# Sheet2.net
KiCad netlist of a schematic drawn in Altium Designer
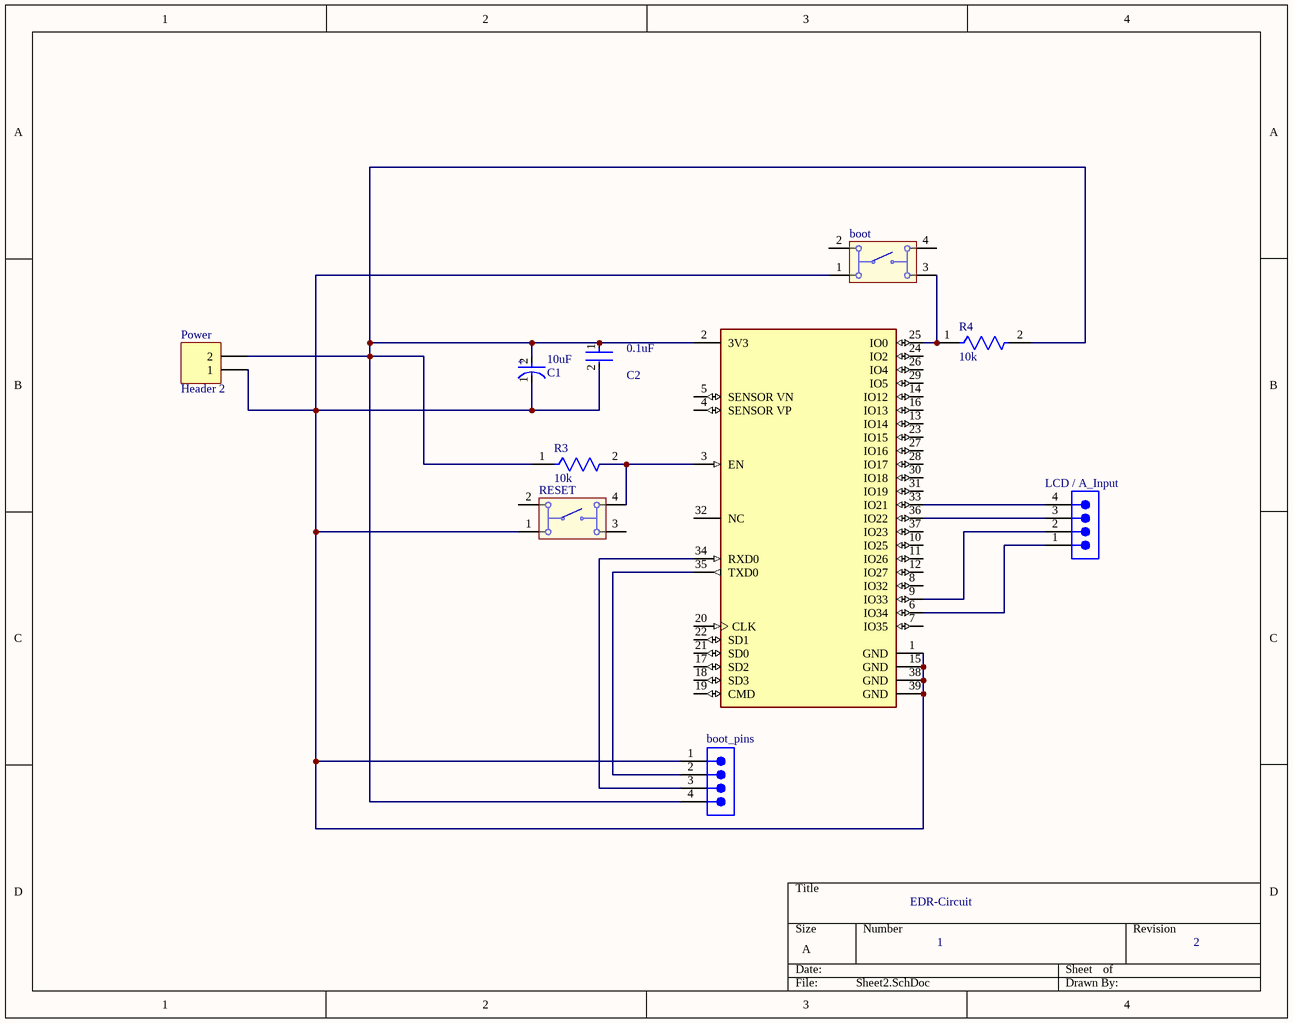
[diagram p0: Sheet2.SchDoc]

(export (version "E")
  (design (tool "Eeschema 10.0.6"))
  (components
    (comp (ref "0.1uF")
      (value "C2")
      (footprint "FP-RCE0DB-MFG")
      (description "Cap Ceramic 100nF 50V X7R ±10% Radial 2.5mm +125°C Ammo Pack")
      (fields (field (name "TOLERANCE") "10%"))
      (libsource (lib "Altium Content Vault") (part "b4654b650e69147ec39a6b967a45e02"))
    )
    (comp (ref "10uF")
      (value "C1")
      (footprint "FP-RAD-TH-D_10_0_5-L_16_1-MFG")
      (description "Aluminum Electrolytic Capacitors (Radial Lead Type) AEC-Q200 Qualified 1000uF ±20% 10V")
      (fields (field (name "VOLTAGE") "10V") (field (name "TOLERANCE") "20%"))
      (libsource (lib "Altium Content Vault") (part "a00bbbee19879c290e62620ae7e47b1"))
    )
    (comp (ref "boot")
      (value "430471025826")
      (footprint "430471025826")
      (description "WS-TASV SMD Tact Switch 6X6 mm")
      (fields (field (name "MANUFACTURER") "Wuerth Elektronik"))
      (libsource (lib "Altium Content Vault") (part "WE-TACT-SW-4_A"))
    )
    (comp (ref "boot_pins")
      (value "TSW-104-08-L-S")
      (footprint "SMTC-TSW-104-08-X-S")
      (description "0.025\" SQ Post Header, Through-hole, Vertical, -55 to 125 degC, 2.54 mm Pitch, 4-Pin, Male, RoHS")
      (fields (field (name "MANUFACTURER") "Samtec"))
      (libsource (lib "Altium Content Vault") (part "SMTC-TSW-104-08-X-S"))
    )
    (comp (ref "esp32")
      (value "ESP32-WROOM-32D")
      (footprint "FP-ESP32-WROOM-32D-MFG")
      (description "WIFI MODULE 32MBITS SPI FLASH")
      (fields
        (field (name "OCTOPART") "https://octopart.com/esp32-wroom-32d-espressif+systems-91040050")
        (field (name "MANUFACTURER") "Espressif Systems")
      )
      (libsource (lib "Altium Content Vault") (part "a031a76f8c27026a7a7f4657ff233a3"))
    )
    (comp (ref "LCD / A_Input")
      (value "TSW-104-08-L-S")
      (footprint "SMTC-TSW-104-08-X-S")
      (description "0.025\" SQ Post Header, Through-hole, Vertical, -55 to 125 degC, 2.54 mm Pitch, 4-Pin, Male, RoHS")
      (fields (field (name "MANUFACTURER") "Samtec"))
      (libsource (lib "Altium Content Vault") (part "SMTC-TSW-104-08-X-S"))
    )
    (comp (ref "Power")
      (value "Header 2")
      (footprint "HDR1X2")
      (description "Header, 2-Pin")
      (fields (field (name "PUBLISHER") "Altium Limited"))
      (libsource (lib "University of Moratuwa") (part "Header 2H"))
    )
    (comp (ref "R3")
      (value "10k")
      (footprint "FP-MBB0207-MFG")
      (description "RES 10K OHM 0.6W 1% AXIAL")
      (fields (field (name "TOLERANCE") "1%"))
      (libsource (lib "Altium Content Vault") (part "1029c3af85768c4190bb7ad29bc67b5"))
    )
    (comp (ref "R4")
      (value "10k")
      (footprint "FP-MBB0207-MFG")
      (description "RES 10K OHM 0.6W 1% AXIAL")
      (fields (field (name "TOLERANCE") "1%"))
      (libsource (lib "Altium Content Vault") (part "1029c3af85768c4190bb7ad29bc67b5"))
    )
    (comp (ref "RESET")
      (value "430471025826")
      (footprint "430471025826")
      (description "WS-TASV SMD Tact Switch 6X6 mm")
      (fields (field (name "MANUFACTURER") "Wuerth Elektronik"))
      (libsource (lib "Altium Content Vault") (part "WE-TACT-SW-4_A"))
    )
  )
  (nets
    (net (code "1") (name "Net-(10uF-A)") (class "Default")
      (node (ref "0.1uF") (pin "1") (pinfunction "1_1") (pintype "passive"))
      (node (ref "10uF") (pin "2") (pinfunction "A_2") (pintype "passive"))
      (node (ref "Power") (pin "2") (pinfunction "2_2") (pintype "passive"))
      (node (ref "R3") (pin "1") (pinfunction "1_1") (pintype "passive"))
      (node (ref "R4") (pin "2") (pinfunction "2_2") (pintype "passive"))
      (node (ref "boot_pins") (pin "4") (pinfunction "4_4") (pintype "passive"))
      (node (ref "esp32") (pin "2") (pinfunction "3V3_2") (pintype "power_in"))
    )
    (net (code "2") (name "Net-(10uF-C)") (class "Default")
      (node (ref "0.1uF") (pin "2") (pinfunction "2_2") (pintype "passive"))
      (node (ref "10uF") (pin "1") (pinfunction "C_1") (pintype "passive"))
      (node (ref "Power") (pin "1") (pinfunction "1_1") (pintype "passive"))
      (node (ref "RESET") (pin "1") (pinfunction "1_1") (pintype "passive"))
      (node (ref "boot") (pin "1") (pinfunction "1_1") (pintype "passive"))
      (node (ref "boot_pins") (pin "1") (pinfunction "1_1") (pintype "passive"))
      (node (ref "esp32") (pin "1") (pinfunction "GND_1") (pintype "power_in"))
      (node (ref "esp32") (pin "15") (pinfunction "GND_15") (pintype "power_in"))
      (node (ref "esp32") (pin "38") (pinfunction "GND_38") (pintype "power_in"))
      (node (ref "esp32") (pin "39") (pinfunction "GND_39") (pintype "power_in"))
    )
    (net (code "3") (name "Net-(esp32-EN)") (class "Default")
      (node (ref "R3") (pin "2") (pinfunction "2_2") (pintype "passive"))
      (node (ref "RESET") (pin "4") (pinfunction "4_4") (pintype "passive"))
      (node (ref "esp32") (pin "3") (pinfunction "EN_3") (pintype "input"))
    )
    (net (code "4") (name "Net-(esp32-IO0)") (class "Default")
      (node (ref "R4") (pin "1") (pinfunction "1_1") (pintype "passive"))
      (node (ref "boot") (pin "3") (pinfunction "3_3") (pintype "passive"))
      (node (ref "esp32") (pin "25") (pinfunction "IO0_25") (pintype "bidirectional"))
    )
    (net (code "5") (name "Net-(esp32-IO21)") (class "Default")
      (node (ref "LCD / A_Input") (pin "4") (pinfunction "4_4") (pintype "passive"))
      (node (ref "esp32") (pin "33") (pinfunction "IO21_33") (pintype "bidirectional"))
    )
    (net (code "6") (name "Net-(esp32-IO22)") (class "Default")
      (node (ref "LCD / A_Input") (pin "3") (pinfunction "3_3") (pintype "passive"))
      (node (ref "esp32") (pin "36") (pinfunction "IO22_36") (pintype "bidirectional"))
    )
    (net (code "7") (name "Net-(esp32-IO33)") (class "Default")
      (node (ref "LCD / A_Input") (pin "2") (pinfunction "2_2") (pintype "passive"))
      (node (ref "esp32") (pin "9") (pinfunction "IO33_9") (pintype "bidirectional"))
    )
    (net (code "8") (name "Net-(esp32-IO34)") (class "Default")
      (node (ref "LCD / A_Input") (pin "1") (pinfunction "1_1") (pintype "passive"))
      (node (ref "esp32") (pin "6") (pinfunction "IO34_6") (pintype "bidirectional"))
    )
    (net (code "9") (name "Net-(esp32-RXD0)") (class "Default")
      (node (ref "boot_pins") (pin "3") (pinfunction "3_3") (pintype "passive"))
      (node (ref "esp32") (pin "34") (pinfunction "RXD0_34") (pintype "input"))
    )
    (net (code "10") (name "Net-(esp32-TXD0)") (class "Default")
      (node (ref "boot_pins") (pin "2") (pinfunction "2_2") (pintype "passive"))
      (node (ref "esp32") (pin "35") (pinfunction "TXD0_35") (pintype "output"))
    )
    (net (code "11") (name "unconnected-(RESET-Pad2)") (class "Default")
      (node (ref "RESET") (pin "2") (pinfunction "2_2") (pintype "passive"))
    )
    (net (code "12") (name "unconnected-(RESET-Pad3)") (class "Default")
      (node (ref "RESET") (pin "3") (pinfunction "3_3") (pintype "passive"))
    )
    (net (code "13") (name "unconnected-(boot-Pad2)") (class "Default")
      (node (ref "boot") (pin "2") (pinfunction "2_2") (pintype "passive"))
    )
    (net (code "14") (name "unconnected-(boot-Pad4)") (class "Default")
      (node (ref "boot") (pin "4") (pinfunction "4_4") (pintype "passive"))
    )
    (net (code "15") (name "unconnected-(esp32-CLK-Pad20)") (class "Default")
      (node (ref "esp32") (pin "20") (pinfunction "CLK_20") (pintype "input"))
    )
    (net (code "16") (name "unconnected-(esp32-CMD-Pad19)") (class "Default")
      (node (ref "esp32") (pin "19") (pinfunction "CMD_19") (pintype "bidirectional"))
    )
    (net (code "17") (name "unconnected-(esp32-IO2-Pad24)") (class "Default")
      (node (ref "esp32") (pin "24") (pinfunction "IO2_24") (pintype "bidirectional"))
    )
    (net (code "18") (name "unconnected-(esp32-IO4-Pad26)") (class "Default")
      (node (ref "esp32") (pin "26") (pinfunction "IO4_26") (pintype "bidirectional"))
    )
    (net (code "19") (name "unconnected-(esp32-IO5-Pad29)") (class "Default")
      (node (ref "esp32") (pin "29") (pinfunction "IO5_29") (pintype "bidirectional"))
    )
    (net (code "20") (name "unconnected-(esp32-IO12-Pad14)") (class "Default")
      (node (ref "esp32") (pin "14") (pinfunction "IO12_14") (pintype "bidirectional"))
    )
    (net (code "21") (name "unconnected-(esp32-IO13-Pad16)") (class "Default")
      (node (ref "esp32") (pin "16") (pinfunction "IO13_16") (pintype "bidirectional"))
    )
    (net (code "22") (name "unconnected-(esp32-IO14-Pad13)") (class "Default")
      (node (ref "esp32") (pin "13") (pinfunction "IO14_13") (pintype "bidirectional"))
    )
    (net (code "23") (name "unconnected-(esp32-IO15-Pad23)") (class "Default")
      (node (ref "esp32") (pin "23") (pinfunction "IO15_23") (pintype "bidirectional"))
    )
    (net (code "24") (name "unconnected-(esp32-IO16-Pad27)") (class "Default")
      (node (ref "esp32") (pin "27") (pinfunction "IO16_27") (pintype "bidirectional"))
    )
    (net (code "25") (name "unconnected-(esp32-IO17-Pad28)") (class "Default")
      (node (ref "esp32") (pin "28") (pinfunction "IO17_28") (pintype "bidirectional"))
    )
    (net (code "26") (name "unconnected-(esp32-IO18-Pad30)") (class "Default")
      (node (ref "esp32") (pin "30") (pinfunction "IO18_30") (pintype "bidirectional"))
    )
    (net (code "27") (name "unconnected-(esp32-IO19-Pad31)") (class "Default")
      (node (ref "esp32") (pin "31") (pinfunction "IO19_31") (pintype "bidirectional"))
    )
    (net (code "28") (name "unconnected-(esp32-IO23-Pad37)") (class "Default")
      (node (ref "esp32") (pin "37") (pinfunction "IO23_37") (pintype "bidirectional"))
    )
    (net (code "29") (name "unconnected-(esp32-IO25-Pad10)") (class "Default")
      (node (ref "esp32") (pin "10") (pinfunction "IO25_10") (pintype "bidirectional"))
    )
    (net (code "30") (name "unconnected-(esp32-IO26-Pad11)") (class "Default")
      (node (ref "esp32") (pin "11") (pinfunction "IO26_11") (pintype "bidirectional"))
    )
    (net (code "31") (name "unconnected-(esp32-IO27-Pad12)") (class "Default")
      (node (ref "esp32") (pin "12") (pinfunction "IO27_12") (pintype "bidirectional"))
    )
    (net (code "32") (name "unconnected-(esp32-IO32-Pad8)") (class "Default")
      (node (ref "esp32") (pin "8") (pinfunction "IO32_8") (pintype "bidirectional"))
    )
    (net (code "33") (name "unconnected-(esp32-IO35-Pad7)") (class "Default")
      (node (ref "esp32") (pin "7") (pinfunction "IO35_7") (pintype "bidirectional"))
    )
    (net (code "34") (name "unconnected-(esp32-NC-Pad32)") (class "Default")
      (node (ref "esp32") (pin "32") (pinfunction "NC_32") (pintype "passive"))
    )
    (net (code "35") (name "unconnected-(esp32-SD0-Pad21)") (class "Default")
      (node (ref "esp32") (pin "21") (pinfunction "SD0_21") (pintype "bidirectional"))
    )
    (net (code "36") (name "unconnected-(esp32-SD1-Pad22)") (class "Default")
      (node (ref "esp32") (pin "22") (pinfunction "SD1_22") (pintype "bidirectional"))
    )
    (net (code "37") (name "unconnected-(esp32-SD2-Pad17)") (class "Default")
      (node (ref "esp32") (pin "17") (pinfunction "SD2_17") (pintype "bidirectional"))
    )
    (net (code "38") (name "unconnected-(esp32-SD3-Pad18)") (class "Default")
      (node (ref "esp32") (pin "18") (pinfunction "SD3_18") (pintype "bidirectional"))
    )
    (net (code "39") (name "unconnected-(esp32-SENSOR_VN-Pad5)") (class "Default")
      (node (ref "esp32") (pin "5") (pinfunction "SENSOR_VN_5") (pintype "bidirectional"))
    )
    (net (code "40") (name "unconnected-(esp32-SENSOR_VP-Pad4)") (class "Default")
      (node (ref "esp32") (pin "4") (pinfunction "SENSOR_VP_4") (pintype "bidirectional"))
    )
  )
)
